# placa.net
KiCad netlist of a schematic drawn in EAGLE
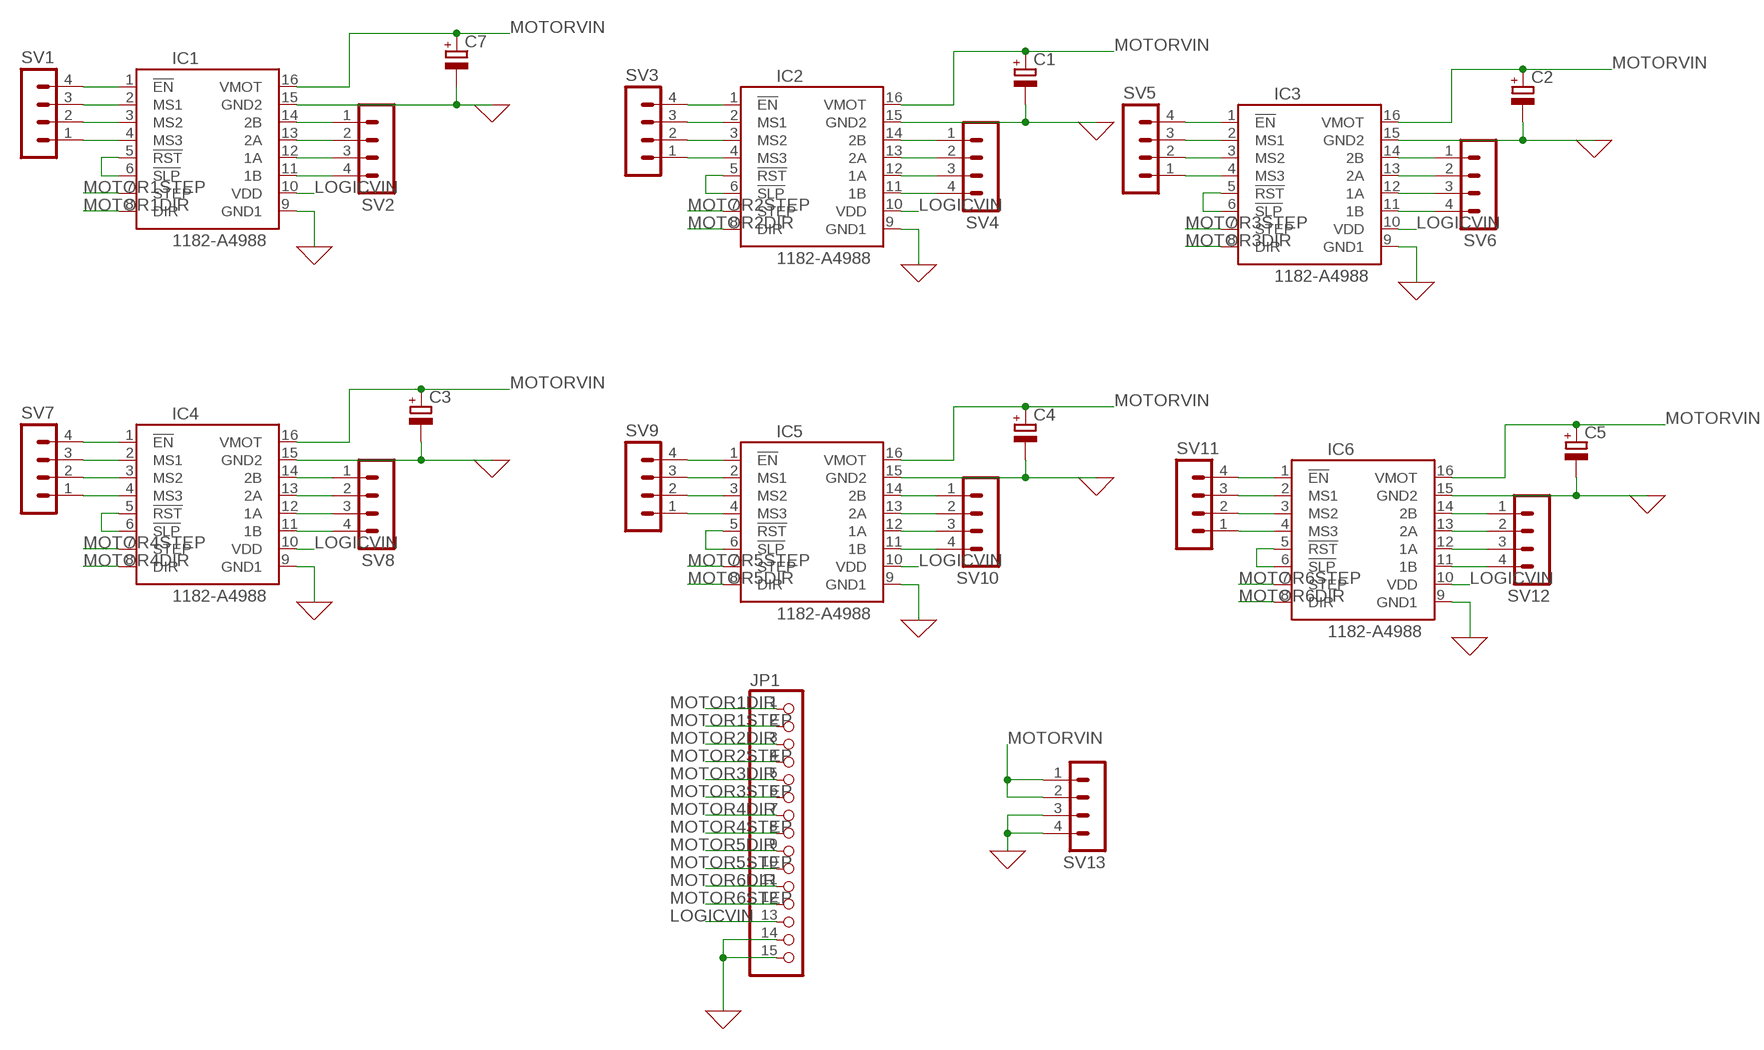
[diagram p0: schematic, sheet 1]

(export (version "E")
  (design (tool "Eeschema 10.0.6"))
  (components
    (comp (ref "C1")
      (value "CPOL-EUE2.5-7")
      (footprint "eagle-import:E2,5-7")
      (libsource (lib "eagle-import") (part "CPOL-EUE2.5-7"))
    )
    (comp (ref "C2")
      (value "CPOL-EUE2.5-7")
      (footprint "eagle-import:E2,5-7")
      (libsource (lib "eagle-import") (part "CPOL-EUE2.5-7"))
    )
    (comp (ref "C3")
      (value "CPOL-EUE2.5-7")
      (footprint "eagle-import:E2,5-7")
      (libsource (lib "eagle-import") (part "CPOL-EUE2.5-7"))
    )
    (comp (ref "C4")
      (value "CPOL-EUE2.5-7")
      (footprint "eagle-import:E2,5-7")
      (libsource (lib "eagle-import") (part "CPOL-EUE2.5-7"))
    )
    (comp (ref "C5")
      (value "CPOL-EUE2.5-7")
      (footprint "eagle-import:E2,5-7")
      (libsource (lib "eagle-import") (part "CPOL-EUE2.5-7"))
    )
    (comp (ref "C7")
      (value "CPOL-EUE2.5-7")
      (footprint "eagle-import:E2,5-7")
      (libsource (lib "eagle-import") (part "CPOL-EUE2.5-7"))
    )
    (comp (ref "IC1")
      (value "1182-A4988")
      (footprint "eagle-import:A4988")
      (libsource (lib "eagle-import") (part "1182-A4988"))
    )
    (comp (ref "IC2")
      (value "1182-A4988")
      (footprint "eagle-import:A4988")
      (libsource (lib "eagle-import") (part "1182-A4988"))
    )
    (comp (ref "IC3")
      (value "1182-A4988")
      (footprint "eagle-import:A4988")
      (libsource (lib "eagle-import") (part "1182-A4988"))
    )
    (comp (ref "IC4")
      (value "1182-A4988")
      (footprint "eagle-import:A4988")
      (libsource (lib "eagle-import") (part "1182-A4988"))
    )
    (comp (ref "IC5")
      (value "1182-A4988")
      (footprint "eagle-import:A4988")
      (libsource (lib "eagle-import") (part "1182-A4988"))
    )
    (comp (ref "IC6")
      (value "1182-A4988")
      (footprint "eagle-import:A4988")
      (libsource (lib "eagle-import") (part "1182-A4988"))
    )
    (comp (ref "JP1")
      (value "PINHD-1X15")
      (footprint "eagle-import:1X15")
      (libsource (lib "eagle-import") (part "PINHD-1X15"))
    )
    (comp (ref "SV1")
      (value "MA04-1")
      (footprint "eagle-import:MA04-1")
      (libsource (lib "eagle-import") (part "MA04-1"))
    )
    (comp (ref "SV2")
      (value "MA04-1")
      (footprint "eagle-import:MA04-1")
      (libsource (lib "eagle-import") (part "MA04-1"))
    )
    (comp (ref "SV3")
      (value "MA04-1")
      (footprint "eagle-import:MA04-1")
      (libsource (lib "eagle-import") (part "MA04-1"))
    )
    (comp (ref "SV4")
      (value "MA04-1")
      (footprint "eagle-import:MA04-1")
      (libsource (lib "eagle-import") (part "MA04-1"))
    )
    (comp (ref "SV5")
      (value "MA04-1")
      (footprint "eagle-import:MA04-1")
      (libsource (lib "eagle-import") (part "MA04-1"))
    )
    (comp (ref "SV6")
      (value "MA04-1")
      (footprint "eagle-import:MA04-1")
      (libsource (lib "eagle-import") (part "MA04-1"))
    )
    (comp (ref "SV7")
      (value "MA04-1")
      (footprint "eagle-import:MA04-1")
      (libsource (lib "eagle-import") (part "MA04-1"))
    )
    (comp (ref "SV8")
      (value "MA04-1")
      (footprint "eagle-import:MA04-1")
      (libsource (lib "eagle-import") (part "MA04-1"))
    )
    (comp (ref "SV9")
      (value "MA04-1")
      (footprint "eagle-import:MA04-1")
      (libsource (lib "eagle-import") (part "MA04-1"))
    )
    (comp (ref "SV10")
      (value "MA04-1")
      (footprint "eagle-import:MA04-1")
      (libsource (lib "eagle-import") (part "MA04-1"))
    )
    (comp (ref "SV11")
      (value "MA04-1")
      (footprint "eagle-import:MA04-1")
      (libsource (lib "eagle-import") (part "MA04-1"))
    )
    (comp (ref "SV12")
      (value "MA04-1")
      (footprint "eagle-import:MA04-1")
      (libsource (lib "eagle-import") (part "MA04-1"))
    )
    (comp (ref "SV13")
      (value "MA04-1")
      (footprint "eagle-import:MA04-1")
      (libsource (lib "eagle-import") (part "MA04-1"))
    )
  )
  (nets
    (net (code "1") (name "/LOGICVIN") (class "Default")
      (node (ref "IC1") (pin "10") (pinfunction "VDD_10") (pintype "power_in"))
      (node (ref "IC2") (pin "10") (pinfunction "VDD_10") (pintype "power_in"))
      (node (ref "IC3") (pin "10") (pinfunction "VDD_10") (pintype "power_in"))
      (node (ref "IC4") (pin "10") (pinfunction "VDD_10") (pintype "power_in"))
      (node (ref "IC5") (pin "10") (pinfunction "VDD_10") (pintype "power_in"))
      (node (ref "IC6") (pin "10") (pinfunction "VDD_10") (pintype "power_in"))
      (node (ref "JP1") (pin "13") (pinfunction "13_13") (pintype "passive"))
    )
    (net (code "2") (name "/MOTOR1DIR") (class "Default")
      (node (ref "IC1") (pin "8") (pinfunction "DIR_8") (pintype "input"))
      (node (ref "JP1") (pin "1") (pinfunction "1_1") (pintype "passive"))
    )
    (net (code "3") (name "/MOTOR1STEP") (class "Default")
      (node (ref "IC1") (pin "7") (pinfunction "STEP_7") (pintype "input"))
      (node (ref "JP1") (pin "2") (pinfunction "2_2") (pintype "passive"))
    )
    (net (code "4") (name "/MOTOR2DIR") (class "Default")
      (node (ref "IC2") (pin "8") (pinfunction "DIR_8") (pintype "input"))
      (node (ref "JP1") (pin "3") (pinfunction "3_3") (pintype "passive"))
    )
    (net (code "5") (name "/MOTOR2STEP") (class "Default")
      (node (ref "IC2") (pin "7") (pinfunction "STEP_7") (pintype "input"))
      (node (ref "JP1") (pin "4") (pinfunction "4_4") (pintype "passive"))
    )
    (net (code "6") (name "/MOTOR3DIR") (class "Default")
      (node (ref "IC3") (pin "8") (pinfunction "DIR_8") (pintype "input"))
      (node (ref "JP1") (pin "5") (pinfunction "5_5") (pintype "passive"))
    )
    (net (code "7") (name "/MOTOR3STEP") (class "Default")
      (node (ref "IC3") (pin "7") (pinfunction "STEP_7") (pintype "input"))
      (node (ref "JP1") (pin "6") (pinfunction "6_6") (pintype "passive"))
    )
    (net (code "8") (name "/MOTOR4DIR") (class "Default")
      (node (ref "IC4") (pin "8") (pinfunction "DIR_8") (pintype "input"))
      (node (ref "JP1") (pin "7") (pinfunction "7_7") (pintype "passive"))
    )
    (net (code "9") (name "/MOTOR4STEP") (class "Default")
      (node (ref "IC4") (pin "7") (pinfunction "STEP_7") (pintype "input"))
      (node (ref "JP1") (pin "8") (pinfunction "8_8") (pintype "passive"))
    )
    (net (code "10") (name "/MOTOR5DIR") (class "Default")
      (node (ref "IC5") (pin "8") (pinfunction "DIR_8") (pintype "input"))
      (node (ref "JP1") (pin "9") (pinfunction "9_9") (pintype "passive"))
    )
    (net (code "11") (name "/MOTOR5STEP") (class "Default")
      (node (ref "IC5") (pin "7") (pinfunction "STEP_7") (pintype "input"))
      (node (ref "JP1") (pin "10") (pinfunction "10_10") (pintype "passive"))
    )
    (net (code "12") (name "/MOTOR6DIR") (class "Default")
      (node (ref "IC6") (pin "8") (pinfunction "DIR_8") (pintype "input"))
      (node (ref "JP1") (pin "11") (pinfunction "11_11") (pintype "passive"))
    )
    (net (code "13") (name "/MOTOR6STEP") (class "Default")
      (node (ref "IC6") (pin "7") (pinfunction "STEP_7") (pintype "input"))
      (node (ref "JP1") (pin "12") (pinfunction "12_12") (pintype "passive"))
    )
    (net (code "14") (name "/MOTORVIN") (class "Default")
      (node (ref "C1") (pin "+") (pinfunction "+_+") (pintype "passive"))
      (node (ref "C2") (pin "+") (pinfunction "+_+") (pintype "passive"))
      (node (ref "C3") (pin "+") (pinfunction "+_+") (pintype "passive"))
      (node (ref "C4") (pin "+") (pinfunction "+_+") (pintype "passive"))
      (node (ref "C5") (pin "+") (pinfunction "+_+") (pintype "passive"))
      (node (ref "C7") (pin "+") (pinfunction "+_+") (pintype "passive"))
      (node (ref "IC1") (pin "16") (pinfunction "VMOT_16") (pintype "power_in"))
      (node (ref "IC2") (pin "16") (pinfunction "VMOT_16") (pintype "power_in"))
      (node (ref "IC3") (pin "16") (pinfunction "VMOT_16") (pintype "power_in"))
      (node (ref "IC4") (pin "16") (pinfunction "VMOT_16") (pintype "power_in"))
      (node (ref "IC5") (pin "16") (pinfunction "VMOT_16") (pintype "power_in"))
      (node (ref "IC6") (pin "16") (pinfunction "VMOT_16") (pintype "power_in"))
      (node (ref "SV13") (pin "1") (pinfunction "1_1") (pintype "passive"))
      (node (ref "SV13") (pin "2") (pinfunction "2_2") (pintype "passive"))
    )
    (net (code "15") (name "GND") (class "Default")
      (node (ref "C1") (pin "-") (pinfunction "-_-") (pintype "passive"))
      (node (ref "C2") (pin "-") (pinfunction "-_-") (pintype "passive"))
      (node (ref "C3") (pin "-") (pinfunction "-_-") (pintype "passive"))
      (node (ref "C4") (pin "-") (pinfunction "-_-") (pintype "passive"))
      (node (ref "C5") (pin "-") (pinfunction "-_-") (pintype "passive"))
      (node (ref "C7") (pin "-") (pinfunction "-_-") (pintype "passive"))
      (node (ref "IC1") (pin "15") (pinfunction "GND2_15") (pintype "power_in"))
      (node (ref "IC1") (pin "9") (pinfunction "GND1_9") (pintype "power_in"))
      (node (ref "IC2") (pin "15") (pinfunction "GND2_15") (pintype "power_in"))
      (node (ref "IC2") (pin "9") (pinfunction "GND1_9") (pintype "power_in"))
      (node (ref "IC3") (pin "15") (pinfunction "GND2_15") (pintype "power_in"))
      (node (ref "IC3") (pin "9") (pinfunction "GND1_9") (pintype "power_in"))
      (node (ref "IC4") (pin "15") (pinfunction "GND2_15") (pintype "power_in"))
      (node (ref "IC4") (pin "9") (pinfunction "GND1_9") (pintype "power_in"))
      (node (ref "IC5") (pin "15") (pinfunction "GND2_15") (pintype "power_in"))
      (node (ref "IC5") (pin "9") (pinfunction "GND1_9") (pintype "power_in"))
      (node (ref "IC6") (pin "15") (pinfunction "GND2_15") (pintype "power_in"))
      (node (ref "IC6") (pin "9") (pinfunction "GND1_9") (pintype "power_in"))
      (node (ref "JP1") (pin "14") (pinfunction "14_14") (pintype "passive"))
      (node (ref "JP1") (pin "15") (pinfunction "15_15") (pintype "passive"))
      (node (ref "SV13") (pin "3") (pinfunction "3_3") (pintype "passive"))
      (node (ref "SV13") (pin "4") (pinfunction "4_4") (pintype "passive"))
    )
    (net (code "16") (name "Net-(IC1-1A)") (class "Default")
      (node (ref "IC1") (pin "12") (pinfunction "1A_12") (pintype "output"))
      (node (ref "SV2") (pin "3") (pinfunction "3_3") (pintype "passive"))
    )
    (net (code "17") (name "Net-(IC1-1B)") (class "Default")
      (node (ref "IC1") (pin "11") (pinfunction "1B_11") (pintype "output"))
      (node (ref "SV2") (pin "4") (pinfunction "4_4") (pintype "passive"))
    )
    (net (code "18") (name "Net-(IC1-2A)") (class "Default")
      (node (ref "IC1") (pin "13") (pinfunction "2A_13") (pintype "output"))
      (node (ref "SV2") (pin "2") (pinfunction "2_2") (pintype "passive"))
    )
    (net (code "19") (name "Net-(IC1-2B)") (class "Default")
      (node (ref "IC1") (pin "14") (pinfunction "2B_14") (pintype "output"))
      (node (ref "SV2") (pin "1") (pinfunction "1_1") (pintype "passive"))
    )
    (net (code "20") (name "Net-(IC1-MS1)") (class "Default")
      (node (ref "IC1") (pin "2") (pinfunction "MS1_2") (pintype "passive"))
      (node (ref "SV1") (pin "3") (pinfunction "3_3") (pintype "passive"))
    )
    (net (code "21") (name "Net-(IC1-MS2)") (class "Default")
      (node (ref "IC1") (pin "3") (pinfunction "MS2_3") (pintype "passive"))
      (node (ref "SV1") (pin "2") (pinfunction "2_2") (pintype "passive"))
    )
    (net (code "22") (name "Net-(IC1-MS3)") (class "Default")
      (node (ref "IC1") (pin "4") (pinfunction "MS3_4") (pintype "passive"))
      (node (ref "SV1") (pin "1") (pinfunction "1_1") (pintype "passive"))
    )
    (net (code "23") (name "Net-(IC1-~{EN})") (class "Default")
      (node (ref "IC1") (pin "1") (pinfunction "~{EN}_1") (pintype "passive"))
      (node (ref "SV1") (pin "4") (pinfunction "4_4") (pintype "passive"))
    )
    (net (code "24") (name "Net-(IC1-~{RST})") (class "Default")
      (node (ref "IC1") (pin "5") (pinfunction "~{RST}_5") (pintype "passive"))
      (node (ref "IC1") (pin "6") (pinfunction "~{SLP}_6") (pintype "passive"))
    )
    (net (code "25") (name "Net-(IC2-1A)") (class "Default")
      (node (ref "IC2") (pin "12") (pinfunction "1A_12") (pintype "output"))
      (node (ref "SV4") (pin "3") (pinfunction "3_3") (pintype "passive"))
    )
    (net (code "26") (name "Net-(IC2-1B)") (class "Default")
      (node (ref "IC2") (pin "11") (pinfunction "1B_11") (pintype "output"))
      (node (ref "SV4") (pin "4") (pinfunction "4_4") (pintype "passive"))
    )
    (net (code "27") (name "Net-(IC2-2A)") (class "Default")
      (node (ref "IC2") (pin "13") (pinfunction "2A_13") (pintype "output"))
      (node (ref "SV4") (pin "2") (pinfunction "2_2") (pintype "passive"))
    )
    (net (code "28") (name "Net-(IC2-2B)") (class "Default")
      (node (ref "IC2") (pin "14") (pinfunction "2B_14") (pintype "output"))
      (node (ref "SV4") (pin "1") (pinfunction "1_1") (pintype "passive"))
    )
    (net (code "29") (name "Net-(IC2-MS1)") (class "Default")
      (node (ref "IC2") (pin "2") (pinfunction "MS1_2") (pintype "passive"))
      (node (ref "SV3") (pin "3") (pinfunction "3_3") (pintype "passive"))
    )
    (net (code "30") (name "Net-(IC2-MS2)") (class "Default")
      (node (ref "IC2") (pin "3") (pinfunction "MS2_3") (pintype "passive"))
      (node (ref "SV3") (pin "2") (pinfunction "2_2") (pintype "passive"))
    )
    (net (code "31") (name "Net-(IC2-MS3)") (class "Default")
      (node (ref "IC2") (pin "4") (pinfunction "MS3_4") (pintype "passive"))
      (node (ref "SV3") (pin "1") (pinfunction "1_1") (pintype "passive"))
    )
    (net (code "32") (name "Net-(IC2-~{EN})") (class "Default")
      (node (ref "IC2") (pin "1") (pinfunction "~{EN}_1") (pintype "passive"))
      (node (ref "SV3") (pin "4") (pinfunction "4_4") (pintype "passive"))
    )
    (net (code "33") (name "Net-(IC2-~{RST})") (class "Default")
      (node (ref "IC2") (pin "5") (pinfunction "~{RST}_5") (pintype "passive"))
      (node (ref "IC2") (pin "6") (pinfunction "~{SLP}_6") (pintype "passive"))
    )
    (net (code "34") (name "Net-(IC3-1A)") (class "Default")
      (node (ref "IC3") (pin "12") (pinfunction "1A_12") (pintype "output"))
      (node (ref "SV6") (pin "3") (pinfunction "3_3") (pintype "passive"))
    )
    (net (code "35") (name "Net-(IC3-1B)") (class "Default")
      (node (ref "IC3") (pin "11") (pinfunction "1B_11") (pintype "output"))
      (node (ref "SV6") (pin "4") (pinfunction "4_4") (pintype "passive"))
    )
    (net (code "36") (name "Net-(IC3-2A)") (class "Default")
      (node (ref "IC3") (pin "13") (pinfunction "2A_13") (pintype "output"))
      (node (ref "SV6") (pin "2") (pinfunction "2_2") (pintype "passive"))
    )
    (net (code "37") (name "Net-(IC3-2B)") (class "Default")
      (node (ref "IC3") (pin "14") (pinfunction "2B_14") (pintype "output"))
      (node (ref "SV6") (pin "1") (pinfunction "1_1") (pintype "passive"))
    )
    (net (code "38") (name "Net-(IC3-MS1)") (class "Default")
      (node (ref "IC3") (pin "2") (pinfunction "MS1_2") (pintype "passive"))
      (node (ref "SV5") (pin "3") (pinfunction "3_3") (pintype "passive"))
    )
    (net (code "39") (name "Net-(IC3-MS2)") (class "Default")
      (node (ref "IC3") (pin "3") (pinfunction "MS2_3") (pintype "passive"))
      (node (ref "SV5") (pin "2") (pinfunction "2_2") (pintype "passive"))
    )
    (net (code "40") (name "Net-(IC3-MS3)") (class "Default")
      (node (ref "IC3") (pin "4") (pinfunction "MS3_4") (pintype "passive"))
      (node (ref "SV5") (pin "1") (pinfunction "1_1") (pintype "passive"))
    )
    (net (code "41") (name "Net-(IC3-~{EN})") (class "Default")
      (node (ref "IC3") (pin "1") (pinfunction "~{EN}_1") (pintype "passive"))
      (node (ref "SV5") (pin "4") (pinfunction "4_4") (pintype "passive"))
    )
    (net (code "42") (name "Net-(IC3-~{RST})") (class "Default")
      (node (ref "IC3") (pin "5") (pinfunction "~{RST}_5") (pintype "passive"))
      (node (ref "IC3") (pin "6") (pinfunction "~{SLP}_6") (pintype "passive"))
    )
    (net (code "43") (name "Net-(IC4-1A)") (class "Default")
      (node (ref "IC4") (pin "12") (pinfunction "1A_12") (pintype "output"))
      (node (ref "SV8") (pin "3") (pinfunction "3_3") (pintype "passive"))
    )
    (net (code "44") (name "Net-(IC4-1B)") (class "Default")
      (node (ref "IC4") (pin "11") (pinfunction "1B_11") (pintype "output"))
      (node (ref "SV8") (pin "4") (pinfunction "4_4") (pintype "passive"))
    )
    (net (code "45") (name "Net-(IC4-2A)") (class "Default")
      (node (ref "IC4") (pin "13") (pinfunction "2A_13") (pintype "output"))
      (node (ref "SV8") (pin "2") (pinfunction "2_2") (pintype "passive"))
    )
    (net (code "46") (name "Net-(IC4-2B)") (class "Default")
      (node (ref "IC4") (pin "14") (pinfunction "2B_14") (pintype "output"))
      (node (ref "SV8") (pin "1") (pinfunction "1_1") (pintype "passive"))
    )
    (net (code "47") (name "Net-(IC4-MS1)") (class "Default")
      (node (ref "IC4") (pin "2") (pinfunction "MS1_2") (pintype "passive"))
      (node (ref "SV7") (pin "3") (pinfunction "3_3") (pintype "passive"))
    )
    (net (code "48") (name "Net-(IC4-MS2)") (class "Default")
      (node (ref "IC4") (pin "3") (pinfunction "MS2_3") (pintype "passive"))
      (node (ref "SV7") (pin "2") (pinfunction "2_2") (pintype "passive"))
    )
    (net (code "49") (name "Net-(IC4-MS3)") (class "Default")
      (node (ref "IC4") (pin "4") (pinfunction "MS3_4") (pintype "passive"))
      (node (ref "SV7") (pin "1") (pinfunction "1_1") (pintype "passive"))
    )
    (net (code "50") (name "Net-(IC4-~{EN})") (class "Default")
      (node (ref "IC4") (pin "1") (pinfunction "~{EN}_1") (pintype "passive"))
      (node (ref "SV7") (pin "4") (pinfunction "4_4") (pintype "passive"))
    )
    (net (code "51") (name "Net-(IC4-~{RST})") (class "Default")
      (node (ref "IC4") (pin "5") (pinfunction "~{RST}_5") (pintype "passive"))
      (node (ref "IC4") (pin "6") (pinfunction "~{SLP}_6") (pintype "passive"))
    )
    (net (code "52") (name "Net-(IC5-1A)") (class "Default")
      (node (ref "IC5") (pin "12") (pinfunction "1A_12") (pintype "output"))
      (node (ref "SV10") (pin "3") (pinfunction "3_3") (pintype "passive"))
    )
    (net (code "53") (name "Net-(IC5-1B)") (class "Default")
      (node (ref "IC5") (pin "11") (pinfunction "1B_11") (pintype "output"))
      (node (ref "SV10") (pin "4") (pinfunction "4_4") (pintype "passive"))
    )
    (net (code "54") (name "Net-(IC5-2A)") (class "Default")
      (node (ref "IC5") (pin "13") (pinfunction "2A_13") (pintype "output"))
      (node (ref "SV10") (pin "2") (pinfunction "2_2") (pintype "passive"))
    )
    (net (code "55") (name "Net-(IC5-2B)") (class "Default")
      (node (ref "IC5") (pin "14") (pinfunction "2B_14") (pintype "output"))
      (node (ref "SV10") (pin "1") (pinfunction "1_1") (pintype "passive"))
    )
    (net (code "56") (name "Net-(IC5-MS1)") (class "Default")
      (node (ref "IC5") (pin "2") (pinfunction "MS1_2") (pintype "passive"))
      (node (ref "SV9") (pin "3") (pinfunction "3_3") (pintype "passive"))
    )
    (net (code "57") (name "Net-(IC5-MS2)") (class "Default")
      (node (ref "IC5") (pin "3") (pinfunction "MS2_3") (pintype "passive"))
      (node (ref "SV9") (pin "2") (pinfunction "2_2") (pintype "passive"))
    )
    (net (code "58") (name "Net-(IC5-MS3)") (class "Default")
      (node (ref "IC5") (pin "4") (pinfunction "MS3_4") (pintype "passive"))
      (node (ref "SV9") (pin "1") (pinfunction "1_1") (pintype "passive"))
    )
    (net (code "59") (name "Net-(IC5-~{EN})") (class "Default")
      (node (ref "IC5") (pin "1") (pinfunction "~{EN}_1") (pintype "passive"))
      (node (ref "SV9") (pin "4") (pinfunction "4_4") (pintype "passive"))
    )
    (net (code "60") (name "Net-(IC5-~{RST})") (class "Default")
      (node (ref "IC5") (pin "5") (pinfunction "~{RST}_5") (pintype "passive"))
      (node (ref "IC5") (pin "6") (pinfunction "~{SLP}_6") (pintype "passive"))
    )
    (net (code "61") (name "Net-(IC6-1A)") (class "Default")
      (node (ref "IC6") (pin "12") (pinfunction "1A_12") (pintype "output"))
      (node (ref "SV12") (pin "3") (pinfunction "3_3") (pintype "passive"))
    )
    (net (code "62") (name "Net-(IC6-1B)") (class "Default")
      (node (ref "IC6") (pin "11") (pinfunction "1B_11") (pintype "output"))
      (node (ref "SV12") (pin "4") (pinfunction "4_4") (pintype "passive"))
    )
    (net (code "63") (name "Net-(IC6-2A)") (class "Default")
      (node (ref "IC6") (pin "13") (pinfunction "2A_13") (pintype "output"))
      (node (ref "SV12") (pin "2") (pinfunction "2_2") (pintype "passive"))
    )
    (net (code "64") (name "Net-(IC6-2B)") (class "Default")
      (node (ref "IC6") (pin "14") (pinfunction "2B_14") (pintype "output"))
      (node (ref "SV12") (pin "1") (pinfunction "1_1") (pintype "passive"))
    )
    (net (code "65") (name "Net-(IC6-MS1)") (class "Default")
      (node (ref "IC6") (pin "2") (pinfunction "MS1_2") (pintype "passive"))
      (node (ref "SV11") (pin "3") (pinfunction "3_3") (pintype "passive"))
    )
    (net (code "66") (name "Net-(IC6-MS2)") (class "Default")
      (node (ref "IC6") (pin "3") (pinfunction "MS2_3") (pintype "passive"))
      (node (ref "SV11") (pin "2") (pinfunction "2_2") (pintype "passive"))
    )
    (net (code "67") (name "Net-(IC6-MS3)") (class "Default")
      (node (ref "IC6") (pin "4") (pinfunction "MS3_4") (pintype "passive"))
      (node (ref "SV11") (pin "1") (pinfunction "1_1") (pintype "passive"))
    )
    (net (code "68") (name "Net-(IC6-~{EN})") (class "Default")
      (node (ref "IC6") (pin "1") (pinfunction "~{EN}_1") (pintype "passive"))
      (node (ref "SV11") (pin "4") (pinfunction "4_4") (pintype "passive"))
    )
    (net (code "69") (name "Net-(IC6-~{RST})") (class "Default")
      (node (ref "IC6") (pin "5") (pinfunction "~{RST}_5") (pintype "passive"))
      (node (ref "IC6") (pin "6") (pinfunction "~{SLP}_6") (pintype "passive"))
    )
  )
)
